# tl4242-driver-20mm-mk-2.net
KiCad netlist of a schematic drawn in EAGLE
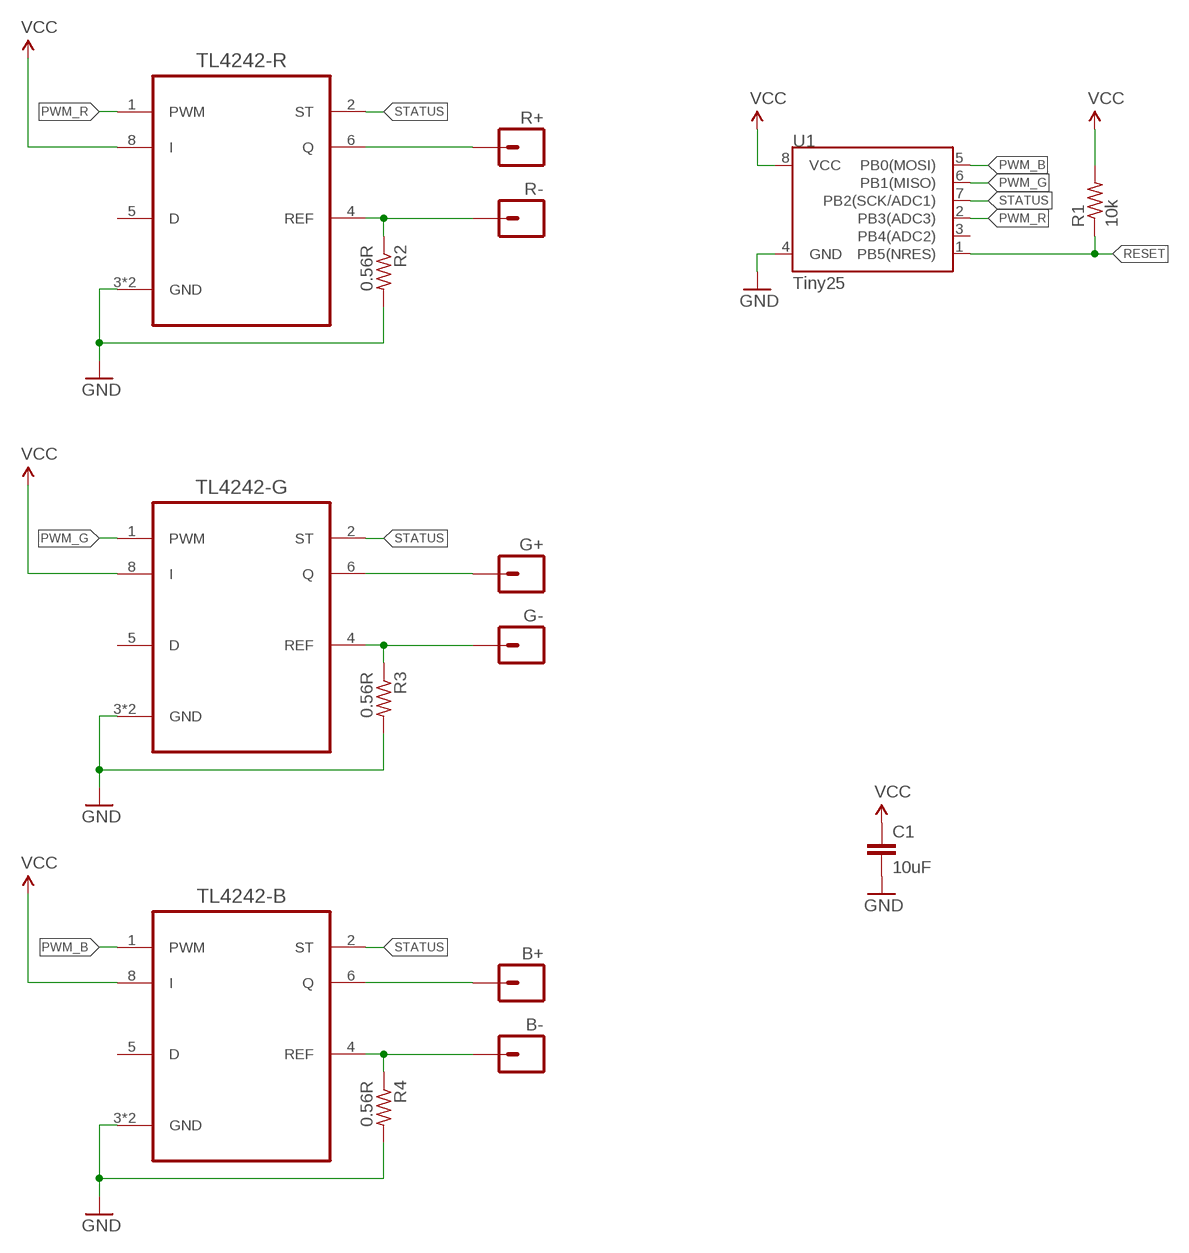
[diagram p0: schematic, sheet 1]

(export (version "E")
  (design (tool "Eeschema 10.0.6"))
  (components
    (comp (ref "B+")
      (value "M01PTH-0.65MM-NS")
      (footprint "eagle-import:1X01_635UM")
      (libsource (lib "eagle-import") (part "M01PTH-0.65MM-NS"))
    )
    (comp (ref "B-")
      (value "M01PTH-0.65MM-NS")
      (footprint "eagle-import:1X01_635UM")
      (libsource (lib "eagle-import") (part "M01PTH-0.65MM-NS"))
    )
    (comp (ref "C1")
      (value "10uF")
      (footprint "eagle-import:C0805")
      (libsource (lib "eagle-import") (part "CAPACITOR-CERAMICC0805"))
    )
    (comp (ref "G+")
      (value "M01PTH-0.65MM-NS")
      (footprint "eagle-import:1X01_635UM")
      (libsource (lib "eagle-import") (part "M01PTH-0.65MM-NS"))
    )
    (comp (ref "G-")
      (value "M01PTH-0.65MM-NS")
      (footprint "eagle-import:1X01_635UM")
      (libsource (lib "eagle-import") (part "M01PTH-0.65MM-NS"))
    )
    (comp (ref "R+")
      (value "M01PTH-0.65MM-NS")
      (footprint "eagle-import:1X01_635UM")
      (libsource (lib "eagle-import") (part "M01PTH-0.65MM-NS"))
    )
    (comp (ref "R-")
      (value "M01PTH-0.65MM-NS")
      (footprint "eagle-import:1X01_635UM")
      (libsource (lib "eagle-import") (part "M01PTH-0.65MM-NS"))
    )
    (comp (ref "R1")
      (value "10k")
      (footprint "eagle-import:R0402")
      (libsource (lib "eagle-import") (part "RESISTORR0402"))
    )
    (comp (ref "R2")
      (value "0.56R")
      (footprint "eagle-import:R0805")
      (libsource (lib "eagle-import") (part "RESISTORR0805"))
    )
    (comp (ref "R3")
      (value "0.56R")
      (footprint "eagle-import:R0805")
      (libsource (lib "eagle-import") (part "RESISTORR0805"))
    )
    (comp (ref "R4")
      (value "0.56R")
      (footprint "eagle-import:R0805")
      (libsource (lib "eagle-import") (part "RESISTORR0805"))
    )
    (comp (ref "TL4242-B")
      (value "TL4242DRJRSON8")
      (footprint "eagle-import:SON80P410X410X80-9N")
      (fields (field (name "MPN") "TL4242DRJR"))
      (libsource (lib "eagle-import") (part "TL4242DRJRSON8"))
    )
    (comp (ref "TL4242-G")
      (value "TL4242DRJRSON8")
      (footprint "eagle-import:SON80P410X410X80-9N")
      (fields (field (name "MPN") "TL4242DRJR"))
      (libsource (lib "eagle-import") (part "TL4242DRJRSON8"))
    )
    (comp (ref "TL4242-R")
      (value "TL4242DRJRSON8")
      (footprint "eagle-import:SON80P410X410X80-9N")
      (fields (field (name "MPN") "TL4242DRJR"))
      (libsource (lib "eagle-import") (part "TL4242DRJRSON8"))
    )
    (comp (ref "U1")
      (value "Tiny25")
      (footprint "eagle-import:SO08")
      (libsource (lib "eagle-import") (part "ATTINY45TINY25-20-SOICN"))
    )
  )
  (nets
    (net (code "1") (name "GND") (class "Default")
      (node (ref "C1") (pin "2") (pinfunction "2_2") (pintype "passive"))
      (node (ref "R2") (pin "2") (pinfunction "2_2") (pintype "passive"))
      (node (ref "R3") (pin "2") (pinfunction "2_2") (pintype "passive"))
      (node (ref "R4") (pin "2") (pinfunction "2_2") (pintype "passive"))
      (node (ref "TL4242-B") (pin "3") (pinfunction "GND_3") (pintype "passive"))
      (node (ref "TL4242-B") (pin "9") (pinfunction "GND_9") (pintype "passive"))
      (node (ref "TL4242-G") (pin "3") (pinfunction "GND_3") (pintype "passive"))
      (node (ref "TL4242-G") (pin "9") (pinfunction "GND_9") (pintype "passive"))
      (node (ref "TL4242-R") (pin "3") (pinfunction "GND_3") (pintype "passive"))
      (node (ref "TL4242-R") (pin "9") (pinfunction "GND_9") (pintype "passive"))
      (node (ref "U1") (pin "4") (pinfunction "GND_4") (pintype "bidirectional"))
    )
    (net (code "2") (name "Net-(B+-1)") (class "Default")
      (node (ref "B+") (pin "P$1") (pinfunction "1_P$1") (pintype "passive"))
      (node (ref "TL4242-B") (pin "6") (pinfunction "Q_6") (pintype "output"))
    )
    (net (code "3") (name "Net-(B--1)") (class "Default")
      (node (ref "B-") (pin "P$1") (pinfunction "1_P$1") (pintype "passive"))
      (node (ref "R4") (pin "1") (pinfunction "1_1") (pintype "passive"))
      (node (ref "TL4242-B") (pin "4") (pinfunction "REF_4") (pintype "input"))
    )
    (net (code "4") (name "Net-(G+-1)") (class "Default")
      (node (ref "G+") (pin "P$1") (pinfunction "1_P$1") (pintype "passive"))
      (node (ref "TL4242-G") (pin "6") (pinfunction "Q_6") (pintype "output"))
    )
    (net (code "5") (name "Net-(G--1)") (class "Default")
      (node (ref "G-") (pin "P$1") (pinfunction "1_P$1") (pintype "passive"))
      (node (ref "R3") (pin "1") (pinfunction "1_1") (pintype "passive"))
      (node (ref "TL4242-G") (pin "4") (pinfunction "REF_4") (pintype "input"))
    )
    (net (code "6") (name "Net-(R+-1)") (class "Default")
      (node (ref "R+") (pin "P$1") (pinfunction "1_P$1") (pintype "passive"))
      (node (ref "TL4242-R") (pin "6") (pinfunction "Q_6") (pintype "output"))
    )
    (net (code "7") (name "Net-(R--1)") (class "Default")
      (node (ref "R-") (pin "P$1") (pinfunction "1_P$1") (pintype "passive"))
      (node (ref "R2") (pin "1") (pinfunction "1_1") (pintype "passive"))
      (node (ref "TL4242-R") (pin "4") (pinfunction "REF_4") (pintype "input"))
    )
    (net (code "8") (name "PWM_B") (class "Default")
      (node (ref "TL4242-B") (pin "1") (pinfunction "PWM_1") (pintype "input"))
      (node (ref "U1") (pin "5") (pinfunction "PB0(MOSI)_5") (pintype "bidirectional"))
    )
    (net (code "9") (name "PWM_G") (class "Default")
      (node (ref "TL4242-G") (pin "1") (pinfunction "PWM_1") (pintype "input"))
      (node (ref "U1") (pin "6") (pinfunction "PB1(MISO)_6") (pintype "bidirectional"))
    )
    (net (code "10") (name "PWM_R") (class "Default")
      (node (ref "TL4242-R") (pin "1") (pinfunction "PWM_1") (pintype "input"))
      (node (ref "U1") (pin "2") (pinfunction "PB3(ADC3)_2") (pintype "bidirectional"))
    )
    (net (code "11") (name "RESET") (class "Default")
      (node (ref "R1") (pin "1") (pinfunction "1_1") (pintype "passive"))
      (node (ref "U1") (pin "1") (pinfunction "PB5(NRES)_1") (pintype "bidirectional"))
    )
    (net (code "12") (name "STATUS") (class "Default")
      (node (ref "TL4242-B") (pin "2") (pinfunction "ST_2") (pintype "output"))
      (node (ref "TL4242-G") (pin "2") (pinfunction "ST_2") (pintype "output"))
      (node (ref "TL4242-R") (pin "2") (pinfunction "ST_2") (pintype "output"))
      (node (ref "U1") (pin "7") (pinfunction "PB2(SCK/ADC1)_7") (pintype "bidirectional"))
    )
    (net (code "13") (name "VCC") (class "Default")
      (node (ref "C1") (pin "1") (pinfunction "1_1") (pintype "passive"))
      (node (ref "R1") (pin "2") (pinfunction "2_2") (pintype "passive"))
      (node (ref "TL4242-B") (pin "8") (pinfunction "I_8") (pintype "input"))
      (node (ref "TL4242-G") (pin "8") (pinfunction "I_8") (pintype "input"))
      (node (ref "TL4242-R") (pin "8") (pinfunction "I_8") (pintype "input"))
      (node (ref "U1") (pin "8") (pinfunction "VCC_8") (pintype "bidirectional"))
    )
    (net (code "14") (name "unconnected-(TL4242-B-D-Pad5)") (class "Default")
      (node (ref "TL4242-B") (pin "5") (pinfunction "D_5") (pintype "input"))
    )
    (net (code "15") (name "unconnected-(TL4242-G-D-Pad5)") (class "Default")
      (node (ref "TL4242-G") (pin "5") (pinfunction "D_5") (pintype "input"))
    )
    (net (code "16") (name "unconnected-(TL4242-R-D-Pad5)") (class "Default")
      (node (ref "TL4242-R") (pin "5") (pinfunction "D_5") (pintype "input"))
    )
    (net (code "17") (name "unconnected-(U1-PB4(ADC2)-Pad3)") (class "Default")
      (node (ref "U1") (pin "3") (pinfunction "PB4(ADC2)_3") (pintype "bidirectional"))
    )
  )
)
